# AST1011.net
KiCad netlist of a schematic drawn in EAGLE
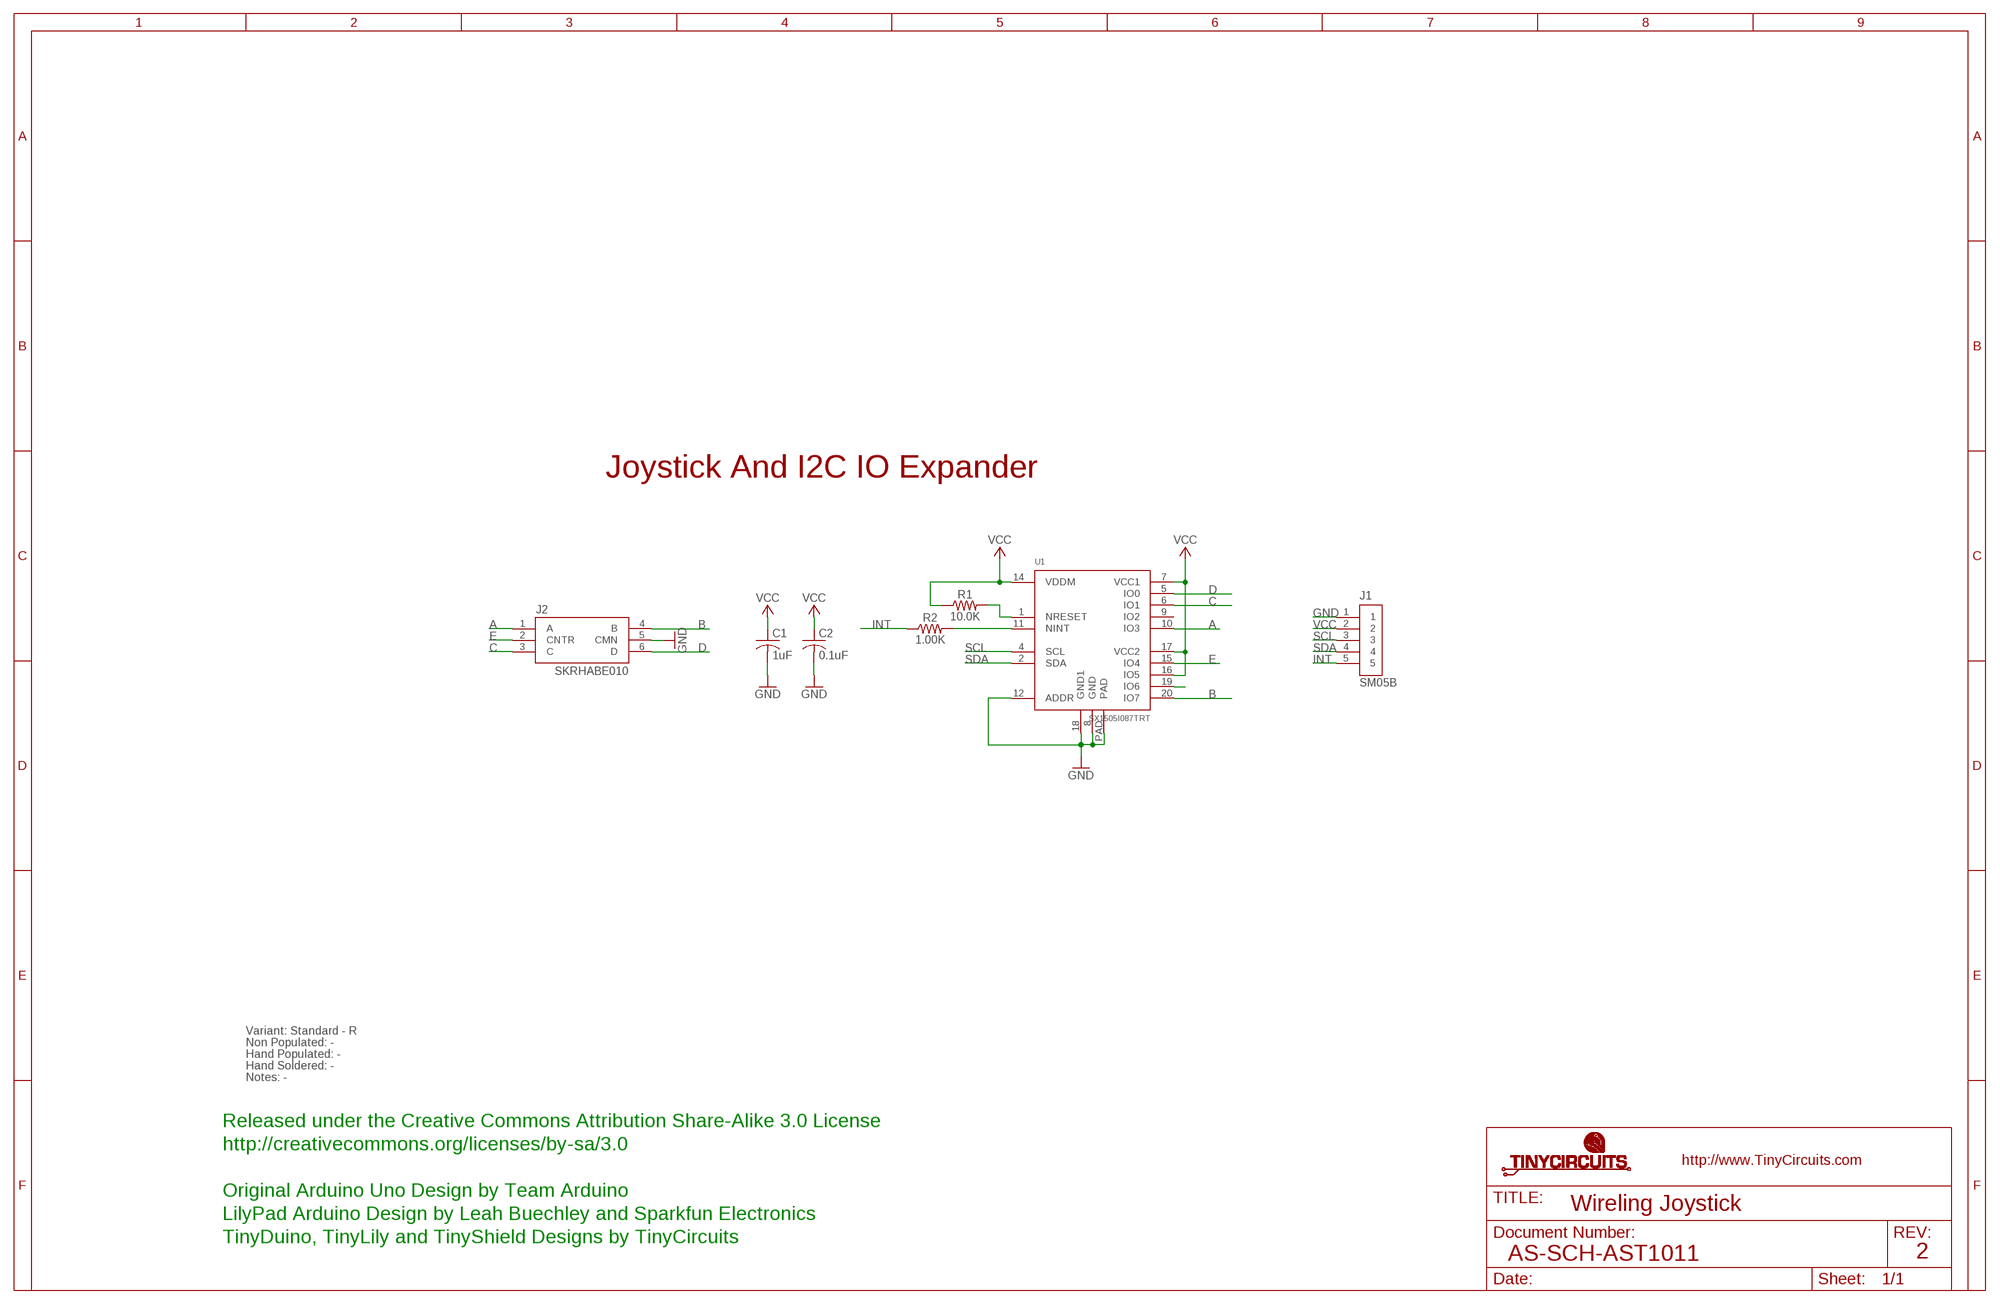
[diagram p0: schematic, sheet 1]

(export (version "E")
  (design (tool "Eeschema 10.0.6"))
  (components
    (comp (ref "C1")
      (value "1uF")
      (footprint "eagle-import:C0402")
      (fields (field (name "PARTNO") "AS-ITM-00105") (field (name "PARTNO_1") "AS-ITM-00105"))
      (libsource (lib "eagle-import") (part "AS-ITM-00105"))
    )
    (comp (ref "C2")
      (value "0.1uF")
      (footprint "eagle-import:C0402")
      (fields (field (name "PARTNO") "AS-ITM-00008"))
      (libsource (lib "eagle-import") (part "AS-ITM-00008"))
    )
    (comp (ref "J1")
      (value "SM05B")
      (footprint "eagle-import:JST_SH_5X1_EDGE")
      (fields (field (name "PARTNO") "AS-ITM-00340"))
      (libsource (lib "eagle-import") (part "AS-ITM-00340EDGE"))
    )
    (comp (ref "J2")
      (value "SKRHABE010")
      (footprint "eagle-import:SKRHA_C")
      (fields (field (name "PARTNO") "AS-ITM-00305"))
      (libsource (lib "eagle-import") (part "AS-ITM-00305A"))
    )
    (comp (ref "R1")
      (value "10.0K")
      (footprint "eagle-import:0402")
      (fields (field (name "PARTNO") "AS-ITM-00032"))
      (libsource (lib "eagle-import") (part "AS-ITM-00032"))
    )
    (comp (ref "R2")
      (value "1.00K")
      (footprint "eagle-import:0402")
      (fields (field (name "PARTNO") "AS-ITM-00003"))
      (libsource (lib "eagle-import") (part "AS-ITM-00003"))
    )
    (comp (ref "U1")
      (value "SX1505I087TRT")
      (footprint "eagle-import:QFN-UT20")
      (fields (field (name "PARTNO") "AS-ITM-00203"))
      (libsource (lib "eagle-import") (part "AS-ITM-00203"))
    )
  )
  (nets
    (net (code "1") (name "/A") (class "Default")
      (node (ref "J2") (pin "1") (pinfunction "A_1") (pintype "bidirectional"))
      (node (ref "U1") (pin "10") (pinfunction "IO3_10") (pintype "bidirectional"))
    )
    (net (code "2") (name "/B") (class "Default")
      (node (ref "J2") (pin "4") (pinfunction "B_4") (pintype "bidirectional"))
      (node (ref "U1") (pin "20") (pinfunction "IO7_20") (pintype "bidirectional"))
    )
    (net (code "3") (name "/C") (class "Default")
      (node (ref "J2") (pin "3") (pinfunction "C_3") (pintype "bidirectional"))
      (node (ref "U1") (pin "6") (pinfunction "IO1_6") (pintype "bidirectional"))
    )
    (net (code "4") (name "/D") (class "Default")
      (node (ref "J2") (pin "6") (pinfunction "D_6") (pintype "bidirectional"))
      (node (ref "U1") (pin "5") (pinfunction "IO0_5") (pintype "bidirectional"))
    )
    (net (code "5") (name "/E") (class "Default")
      (node (ref "J2") (pin "2") (pinfunction "CNTR_2") (pintype "bidirectional"))
      (node (ref "U1") (pin "15") (pinfunction "IO4_15") (pintype "bidirectional"))
    )
    (net (code "6") (name "/INT") (class "Default")
      (node (ref "J1") (pin "5") (pinfunction "5_5") (pintype "bidirectional"))
      (node (ref "R2") (pin "1") (pinfunction "1_1") (pintype "passive"))
    )
    (net (code "7") (name "/SCL") (class "Default")
      (node (ref "J1") (pin "3") (pinfunction "3_3") (pintype "bidirectional"))
      (node (ref "U1") (pin "4") (pinfunction "SCL_4") (pintype "bidirectional"))
    )
    (net (code "8") (name "/SDA") (class "Default")
      (node (ref "J1") (pin "4") (pinfunction "4_4") (pintype "bidirectional"))
      (node (ref "U1") (pin "2") (pinfunction "SDA_2") (pintype "bidirectional"))
    )
    (net (code "9") (name "GND") (class "Default")
      (node (ref "C1") (pin "2") (pinfunction "2_2") (pintype "passive"))
      (node (ref "C2") (pin "2") (pinfunction "2_2") (pintype "passive"))
      (node (ref "J1") (pin "1") (pinfunction "1_1") (pintype "bidirectional"))
      (node (ref "J2") (pin "5") (pinfunction "CMN_5") (pintype "bidirectional"))
      (node (ref "U1") (pin "12") (pinfunction "ADDR_12") (pintype "bidirectional"))
      (node (ref "U1") (pin "18") (pinfunction "GND1_18") (pintype "bidirectional"))
      (node (ref "U1") (pin "8") (pinfunction "GND_8") (pintype "bidirectional"))
      (node (ref "U1") (pin "PAD") (pinfunction "PAD_PAD") (pintype "bidirectional"))
    )
    (net (code "10") (name "Net-(U1-NINT)") (class "Default")
      (node (ref "R2") (pin "2") (pinfunction "2_2") (pintype "passive"))
      (node (ref "U1") (pin "11") (pinfunction "NINT_11") (pintype "bidirectional"))
    )
    (net (code "11") (name "Net-(U1-NRESET)") (class "Default")
      (node (ref "R1") (pin "2") (pinfunction "2_2") (pintype "passive"))
      (node (ref "U1") (pin "1") (pinfunction "NRESET_1") (pintype "bidirectional"))
    )
    (net (code "12") (name "VCC") (class "Default")
      (node (ref "C1") (pin "1") (pinfunction "1_1") (pintype "passive"))
      (node (ref "C2") (pin "1") (pinfunction "1_1") (pintype "passive"))
      (node (ref "J1") (pin "2") (pinfunction "2_2") (pintype "bidirectional"))
      (node (ref "R1") (pin "1") (pinfunction "1_1") (pintype "passive"))
      (node (ref "U1") (pin "14") (pinfunction "VDDM_14") (pintype "bidirectional"))
      (node (ref "U1") (pin "16") (pinfunction "IO5_16") (pintype "bidirectional"))
      (node (ref "U1") (pin "17") (pinfunction "VCC2_17") (pintype "bidirectional"))
      (node (ref "U1") (pin "7") (pinfunction "VCC1_7") (pintype "bidirectional"))
    )
    (net (code "13") (name "unconnected-(U1-IO2-Pad9)") (class "Default")
      (node (ref "U1") (pin "9") (pinfunction "IO2_9") (pintype "bidirectional"))
    )
    (net (code "14") (name "unconnected-(U1-IO6-Pad19)") (class "Default")
      (node (ref "U1") (pin "19") (pinfunction "IO6_19") (pintype "bidirectional"))
    )
  )
)
